# mux-optical.net
KiCad netlist of a schematic drawn in Altium Designer
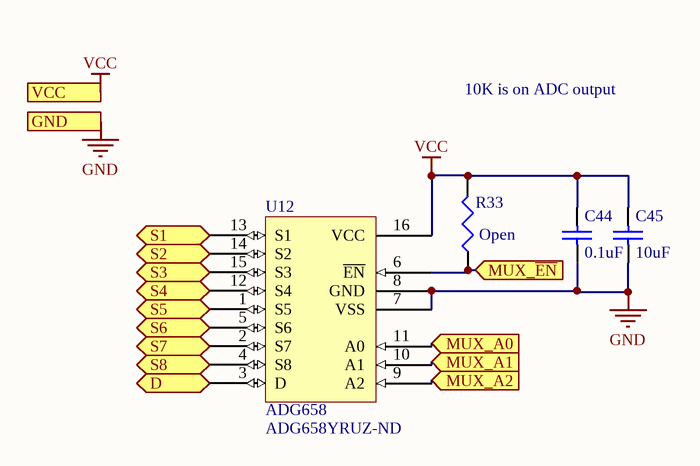
[diagram p0: mux-optical.SchDoc]

(export (version "E")
  (design (tool "Eeschema 10.0.6"))
  (components
    (comp (ref "C44")
      (value "0.1uF")
      (footprint "1608[0603]")
      (description "Capacitor (Semiconductor SIM Model)")
      (fields (field (name "PUBLISHER") "Altium Limited"))
      (libsource (lib "Miscellaneous Devices") (part "Cap Semi"))
    )
    (comp (ref "C45")
      (value "10uF")
      (footprint "1608[0603]")
      (description "Capacitor (Semiconductor SIM Model)")
      (fields (field (name "PUBLISHER") "Altium Limited"))
      (libsource (lib "Miscellaneous Devices") (part "Cap Semi"))
    )
    (comp (ref "R33")
      (value "Open")
      (footprint "J1-0603")
      (description "Resistor")
      (fields (field (name "PUBLISHER") "Altium Limited"))
      (libsource (lib "Miscellaneous Devices") (part "Res3"))
    )
    (comp (ref "U12")
      (value "ADG658")
      (footprint "SSOP16_N")
      (description "Eight channel analog multiplexer.")
      (fields (field (name "SUPPLIER PART NUMBER 1") "ADG658YRUZ-ND"))
      (libsource (lib "PAY") (part "ADG658"))
    )
  )
  (nets
    (net (code "1") (name "/D") (class "Default")
      (node (ref "U12") (pin "3") (pinfunction "D_3") (pintype "bidirectional"))
    )
    (net (code "2") (name "/MUX_A0") (class "Default")
      (node (ref "U12") (pin "11") (pinfunction "A0_11") (pintype "input"))
    )
    (net (code "3") (name "/MUX_A1") (class "Default")
      (node (ref "U12") (pin "10") (pinfunction "A1_10") (pintype "input"))
    )
    (net (code "4") (name "/MUX_A2") (class "Default")
      (node (ref "U12") (pin "9") (pinfunction "A2_9") (pintype "input"))
    )
    (net (code "5") (name "/MUX_~{EN}") (class "Default")
      (node (ref "R33") (pin "1") (pinfunction "1_1") (pintype "passive"))
      (node (ref "U12") (pin "6") (pinfunction "~{EN}_6") (pintype "input"))
    )
    (net (code "6") (name "/S1") (class "Default")
      (node (ref "U12") (pin "13") (pinfunction "S1_13") (pintype "bidirectional"))
    )
    (net (code "7") (name "/S2") (class "Default")
      (node (ref "U12") (pin "14") (pinfunction "S2_14") (pintype "bidirectional"))
    )
    (net (code "8") (name "/S3") (class "Default")
      (node (ref "U12") (pin "15") (pinfunction "S3_15") (pintype "bidirectional"))
    )
    (net (code "9") (name "/S4") (class "Default")
      (node (ref "U12") (pin "12") (pinfunction "S4_12") (pintype "bidirectional"))
    )
    (net (code "10") (name "/S5") (class "Default")
      (node (ref "U12") (pin "1") (pinfunction "S5_1") (pintype "bidirectional"))
    )
    (net (code "11") (name "/S6") (class "Default")
      (node (ref "U12") (pin "5") (pinfunction "S6_5") (pintype "bidirectional"))
    )
    (net (code "12") (name "/S7") (class "Default")
      (node (ref "U12") (pin "2") (pinfunction "S7_2") (pintype "bidirectional"))
    )
    (net (code "13") (name "/S8") (class "Default")
      (node (ref "U12") (pin "4") (pinfunction "S8_4") (pintype "bidirectional"))
    )
    (net (code "14") (name "GND") (class "Default")
      (node (ref "C44") (pin "1") (pinfunction "1_1") (pintype "passive"))
      (node (ref "C45") (pin "1") (pinfunction "1_1") (pintype "passive"))
      (node (ref "U12") (pin "7") (pinfunction "VSS_7") (pintype "power_in"))
      (node (ref "U12") (pin "8") (pinfunction "GND_8") (pintype "power_in"))
    )
    (net (code "15") (name "VCC") (class "Default")
      (node (ref "C44") (pin "2") (pinfunction "2_2") (pintype "passive"))
      (node (ref "C45") (pin "2") (pinfunction "2_2") (pintype "passive"))
      (node (ref "R33") (pin "2") (pinfunction "2_2") (pintype "passive"))
      (node (ref "U12") (pin "16") (pinfunction "VCC_16") (pintype "power_in"))
    )
  )
)
